# P06_DDR3_Memory.net
KiCad netlist of a schematic drawn in Altium Designer
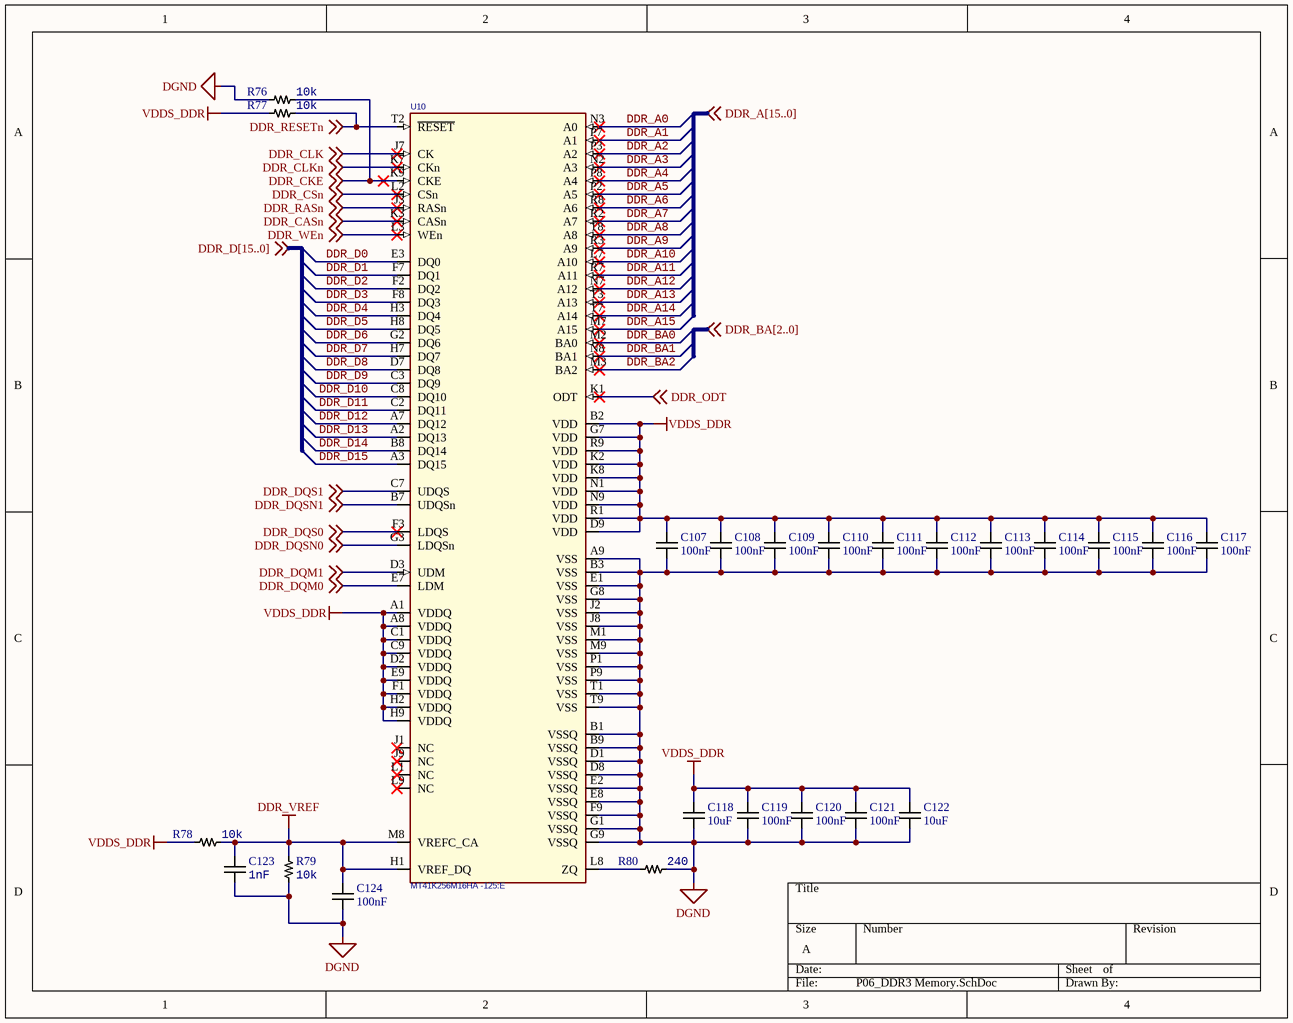
[diagram p0: P06_DDR3 Memory.SchDoc]

(export (version "E")
  (design (tool "Eeschema 10.0.6"))
  (components
    (comp (ref "C107")
      (value "C0402C104K4RACTU")
      (footprint "CAP0402")
      (description "MLCC 100nF 0402 SMD")
      (fields
        (field (name "MANUFACTURER") "KEMET")
        (field (name "CAPACITANCE") "100nF")
        (field (name "TOLERANCE") "10%")
      )
      (libsource (lib "Orient2") (part "CAP_100nF"))
    )
    (comp (ref "C108")
      (value "C0402C104K4RACTU")
      (footprint "CAP0402")
      (description "MLCC 100nF 0402 SMD")
      (fields
        (field (name "MANUFACTURER") "KEMET")
        (field (name "CAPACITANCE") "100nF")
        (field (name "TOLERANCE") "10%")
      )
      (libsource (lib "Orient2") (part "CAP_100nF"))
    )
    (comp (ref "C109")
      (value "C0402C104K4RACTU")
      (footprint "CAP0402")
      (description "MLCC 100nF 0402 SMD")
      (fields
        (field (name "MANUFACTURER") "KEMET")
        (field (name "CAPACITANCE") "100nF")
        (field (name "TOLERANCE") "10%")
      )
      (libsource (lib "Orient2") (part "CAP_100nF"))
    )
    (comp (ref "C110")
      (value "C0402C104K4RACTU")
      (footprint "CAP0402")
      (description "MLCC 100nF 0402 SMD")
      (fields
        (field (name "MANUFACTURER") "KEMET")
        (field (name "CAPACITANCE") "100nF")
        (field (name "TOLERANCE") "10%")
      )
      (libsource (lib "Orient2") (part "CAP_100nF"))
    )
    (comp (ref "C111")
      (value "C0402C104K4RACTU")
      (footprint "CAP0402")
      (description "MLCC 100nF 0402 SMD")
      (fields
        (field (name "MANUFACTURER") "KEMET")
        (field (name "CAPACITANCE") "100nF")
        (field (name "TOLERANCE") "10%")
      )
      (libsource (lib "Orient2") (part "CAP_100nF"))
    )
    (comp (ref "C112")
      (value "C0402C104K4RACTU")
      (footprint "CAP0402")
      (description "MLCC 100nF 0402 SMD")
      (fields
        (field (name "MANUFACTURER") "KEMET")
        (field (name "CAPACITANCE") "100nF")
        (field (name "TOLERANCE") "10%")
      )
      (libsource (lib "Orient2") (part "CAP_100nF"))
    )
    (comp (ref "C113")
      (value "C0402C104K4RACTU")
      (footprint "CAP0402")
      (description "MLCC 100nF 0402 SMD")
      (fields
        (field (name "MANUFACTURER") "KEMET")
        (field (name "CAPACITANCE") "100nF")
        (field (name "TOLERANCE") "10%")
      )
      (libsource (lib "Orient2") (part "CAP_100nF"))
    )
    (comp (ref "C114")
      (value "C0402C104K4RACTU")
      (footprint "CAP0402")
      (description "MLCC 100nF 0402 SMD")
      (fields
        (field (name "MANUFACTURER") "KEMET")
        (field (name "CAPACITANCE") "100nF")
        (field (name "TOLERANCE") "10%")
      )
      (libsource (lib "Orient2") (part "CAP_100nF"))
    )
    (comp (ref "C115")
      (value "C0402C104K4RACTU")
      (footprint "CAP0402")
      (description "MLCC 100nF 0402 SMD")
      (fields
        (field (name "MANUFACTURER") "KEMET")
        (field (name "CAPACITANCE") "100nF")
        (field (name "TOLERANCE") "10%")
      )
      (libsource (lib "Orient2") (part "CAP_100nF"))
    )
    (comp (ref "C116")
      (value "C0402C104K4RACTU")
      (footprint "CAP0402")
      (description "MLCC 100nF 0402 SMD")
      (fields
        (field (name "MANUFACTURER") "KEMET")
        (field (name "CAPACITANCE") "100nF")
        (field (name "TOLERANCE") "10%")
      )
      (libsource (lib "Orient2") (part "CAP_100nF"))
    )
    (comp (ref "C117")
      (value "C0402C104K4RACTU")
      (footprint "CAP0402")
      (description "MLCC 100nF 0402 SMD")
      (fields
        (field (name "MANUFACTURER") "KEMET")
        (field (name "CAPACITANCE") "100nF")
        (field (name "TOLERANCE") "10%")
      )
      (libsource (lib "Orient2") (part "CAP_100nF"))
    )
    (comp (ref "C118")
      (value "C2012X6S1A106K085AC")
      (footprint "CAP0805")
      (description "MLCC 10uF 0805 SMD")
      (fields
        (field (name "MANUFACTURER") "TDK")
        (field (name "CAPACITANCE") "10uF")
        (field (name "TOLERANCE") "10%")
      )
      (libsource (lib "Orient2") (part "CAP_10uF"))
    )
    (comp (ref "C119")
      (value "C0402C104K4RACTU")
      (footprint "CAP0402")
      (description "MLCC 100nF 0402 SMD")
      (fields
        (field (name "MANUFACTURER") "KEMET")
        (field (name "CAPACITANCE") "100nF")
        (field (name "TOLERANCE") "10%")
      )
      (libsource (lib "Orient2") (part "CAP_100nF"))
    )
    (comp (ref "C120")
      (value "C0402C104K4RACTU")
      (footprint "CAP0402")
      (description "MLCC 100nF 0402 SMD")
      (fields
        (field (name "MANUFACTURER") "KEMET")
        (field (name "CAPACITANCE") "100nF")
        (field (name "TOLERANCE") "10%")
      )
      (libsource (lib "Orient2") (part "CAP_100nF"))
    )
    (comp (ref "C121")
      (value "C0402C104K4RACTU")
      (footprint "CAP0402")
      (description "MLCC 100nF 0402 SMD")
      (fields
        (field (name "MANUFACTURER") "KEMET")
        (field (name "CAPACITANCE") "100nF")
        (field (name "TOLERANCE") "10%")
      )
      (libsource (lib "Orient2") (part "CAP_100nF"))
    )
    (comp (ref "C122")
      (value "C2012X6S1A106K085AC")
      (footprint "CAP0805")
      (description "MLCC 10uF 0805 SMD")
      (fields
        (field (name "MANUFACTURER") "TDK")
        (field (name "CAPACITANCE") "10uF")
        (field (name "TOLERANCE") "10%")
      )
      (libsource (lib "Orient2") (part "CAP_10uF"))
    )
    (comp (ref "C123")
      (value "CC0402KRX7R9BB102")
      (footprint "CAP0402")
      (description "MLCC 1nF 0402 SMD")
      (fields
        (field (name "MANUFACTURER") "Yageo")
        (field (name "TOLERANCE") "10%")
        (field (name "CAPACITANCE") "1nF")
      )
      (libsource (lib "Orient2") (part "CAP_1nF"))
    )
    (comp (ref "C124")
      (value "C0402C104K4RACTU")
      (footprint "CAP0402")
      (description "MLCC 100nF 0402 SMD")
      (fields
        (field (name "MANUFACTURER") "KEMET")
        (field (name "CAPACITANCE") "100nF")
        (field (name "TOLERANCE") "10%")
      )
      (libsource (lib "Orient2") (part "CAP_100nF"))
    )
    (comp (ref "R76")
      (value "RC0402FR-0710KL")
      (footprint "RES0402")
      (description "Resistor 10kOhm 0402 SMD")
      (fields
        (field (name "MANUFACTURER") "Yageo")
        (field (name "TOLERANCE") "1%")
        (field (name "RESISTANCE") "10k")
      )
      (libsource (lib "Orient2") (part "RES_10k"))
    )
    (comp (ref "R77")
      (value "RC0402FR-0710KL")
      (footprint "RES0402")
      (description "Resistor 10kOhm 0402 SMD")
      (fields
        (field (name "MANUFACTURER") "Yageo")
        (field (name "TOLERANCE") "1%")
        (field (name "RESISTANCE") "10k")
      )
      (libsource (lib "Orient2") (part "RES_10k"))
    )
    (comp (ref "R78")
      (value "RC0402FR-0710KL")
      (footprint "RES0402")
      (description "Resistor 10kOhm 0402 SMD")
      (fields
        (field (name "MANUFACTURER") "Yageo")
        (field (name "TOLERANCE") "1%")
        (field (name "RESISTANCE") "10k")
      )
      (libsource (lib "Orient2") (part "RES_10k"))
    )
    (comp (ref "R79")
      (value "RC0402FR-0710KL")
      (footprint "RES0402")
      (description "Resistor 10kOhm 0402 SMD")
      (fields
        (field (name "MANUFACTURER") "Yageo")
        (field (name "TOLERANCE") "1%")
        (field (name "RESISTANCE") "10k")
      )
      (libsource (lib "Orient2") (part "RES_10k"))
    )
    (comp (ref "R80")
      (value "RC0402FR-07240RL")
      (footprint "RES0402")
      (description "Resistor 240Ohm 0402 SMD")
      (fields
        (field (name "MANUFACTURER") "Yageo Phycomp")
        (field (name "TOLERANCE") "1%")
        (field (name "RESISTANCE") "240")
      )
      (libsource (lib "Orient2") (part "RES_240"))
    )
    (comp (ref "U10")
      (value "MT41K256M16HA -125:E")
      (footprint "BGA96_T9_P8_9X14")
      (description "DDR2 SDRAM 2Gb (256Mx8)")
      (fields
        (field (name "MANUFACTURER") "Micron Technology")
        (field (name "MANUFACTURER PART NUMBER") "MT41K256M16HA-125:E")
      )
      (libsource (lib "Orient2") (part "MT41K256M16HA"))
    )
  )
  (nets
    (net (code "1") (name "DDR_A0") (class "Default")
      (node (ref "U10") (pin "N3") (pinfunction "A0_N3") (pintype "input+no_connect"))
    )
    (net (code "2") (name "DDR_A1") (class "Default")
      (node (ref "U10") (pin "P7") (pinfunction "A1_P7") (pintype "input+no_connect"))
    )
    (net (code "3") (name "DDR_A2") (class "Default")
      (node (ref "U10") (pin "P3") (pinfunction "A2_P3") (pintype "input+no_connect"))
    )
    (net (code "4") (name "DDR_A3") (class "Default")
      (node (ref "U10") (pin "N2") (pinfunction "A3_N2") (pintype "input+no_connect"))
    )
    (net (code "5") (name "DDR_A4") (class "Default")
      (node (ref "U10") (pin "P8") (pinfunction "A4_P8") (pintype "input+no_connect"))
    )
    (net (code "6") (name "DDR_A5") (class "Default")
      (node (ref "U10") (pin "P2") (pinfunction "A5_P2") (pintype "input+no_connect"))
    )
    (net (code "7") (name "DDR_A6") (class "Default")
      (node (ref "U10") (pin "R8") (pinfunction "A6_R8") (pintype "input+no_connect"))
    )
    (net (code "8") (name "DDR_A7") (class "Default")
      (node (ref "U10") (pin "R2") (pinfunction "A7_R2") (pintype "input+no_connect"))
    )
    (net (code "9") (name "DDR_A8") (class "Default")
      (node (ref "U10") (pin "T8") (pinfunction "A8_T8") (pintype "input+no_connect"))
    )
    (net (code "10") (name "DDR_A9") (class "Default")
      (node (ref "U10") (pin "R3") (pinfunction "A9_R3") (pintype "input+no_connect"))
    )
    (net (code "11") (name "DDR_A10") (class "Default")
      (node (ref "U10") (pin "L7") (pinfunction "A10_L7") (pintype "input+no_connect"))
    )
    (net (code "12") (name "DDR_A11") (class "Default")
      (node (ref "U10") (pin "R7") (pinfunction "A11_R7") (pintype "input+no_connect"))
    )
    (net (code "13") (name "DDR_A12") (class "Default")
      (node (ref "U10") (pin "N7") (pinfunction "A12_N7") (pintype "input+no_connect"))
    )
    (net (code "14") (name "DDR_A13") (class "Default")
      (node (ref "U10") (pin "T3") (pinfunction "A13_T3") (pintype "input+no_connect"))
    )
    (net (code "15") (name "DDR_A14") (class "Default")
      (node (ref "U10") (pin "T7") (pinfunction "A14_T7") (pintype "input+no_connect"))
    )
    (net (code "16") (name "DDR_A15") (class "Default")
      (node (ref "U10") (pin "M7") (pinfunction "A15_M7") (pintype "input+no_connect"))
    )
    (net (code "18") (name "DDR_BA0") (class "Default")
      (node (ref "U10") (pin "M2") (pinfunction "BA0_M2") (pintype "input+no_connect"))
    )
    (net (code "19") (name "DDR_BA1") (class "Default")
      (node (ref "U10") (pin "N8") (pinfunction "BA1_N8") (pintype "input+no_connect"))
    )
    (net (code "20") (name "DDR_BA2") (class "Default")
      (node (ref "U10") (pin "M3") (pinfunction "BA2_M3") (pintype "input+no_connect"))
    )
    (net (code "22") (name "DDR_CASn") (class "Default")
      (node (ref "U10") (pin "K3") (pinfunction "CASn_K3") (pintype "input"))
    )
    (net (code "23") (name "DDR_CKE") (class "Default")
      (node (ref "R76") (pin "1") (pintype "passive"))
      (node (ref "U10") (pin "K9") (pinfunction "CKE_K9") (pintype "input"))
    )
    (net (code "24") (name "DDR_CLK") (class "Default")
      (node (ref "U10") (pin "J7") (pinfunction "CK_J7") (pintype "input"))
    )
    (net (code "25") (name "DDR_CLKn") (class "Default")
      (node (ref "U10") (pin "K7") (pinfunction "CKn_K7") (pintype "input"))
    )
    (net (code "26") (name "DDR_CSn") (class "Default")
      (node (ref "U10") (pin "L2") (pinfunction "CSn_L2") (pintype "input"))
    )
    (net (code "27") (name "DDR_D0") (class "Default")
      (node (ref "U10") (pin "E3") (pinfunction "DQ0_E3") (pintype "bidirectional"))
    )
    (net (code "28") (name "DDR_D1") (class "Default")
      (node (ref "U10") (pin "F7") (pinfunction "DQ1_F7") (pintype "bidirectional"))
    )
    (net (code "29") (name "DDR_D2") (class "Default")
      (node (ref "U10") (pin "F2") (pinfunction "DQ2_F2") (pintype "bidirectional"))
    )
    (net (code "30") (name "DDR_D3") (class "Default")
      (node (ref "U10") (pin "F8") (pinfunction "DQ3_F8") (pintype "bidirectional"))
    )
    (net (code "31") (name "DDR_D4") (class "Default")
      (node (ref "U10") (pin "H3") (pinfunction "DQ4_H3") (pintype "bidirectional"))
    )
    (net (code "32") (name "DDR_D5") (class "Default")
      (node (ref "U10") (pin "H8") (pinfunction "DQ5_H8") (pintype "bidirectional"))
    )
    (net (code "33") (name "DDR_D6") (class "Default")
      (node (ref "U10") (pin "G2") (pinfunction "DQ6_G2") (pintype "bidirectional"))
    )
    (net (code "34") (name "DDR_D7") (class "Default")
      (node (ref "U10") (pin "H7") (pinfunction "DQ7_H7") (pintype "bidirectional"))
    )
    (net (code "35") (name "DDR_D8") (class "Default")
      (node (ref "U10") (pin "D7") (pinfunction "DQ8_D7") (pintype "bidirectional"))
    )
    (net (code "36") (name "DDR_D9") (class "Default")
      (node (ref "U10") (pin "C3") (pinfunction "DQ9_C3") (pintype "bidirectional"))
    )
    (net (code "37") (name "DDR_D10") (class "Default")
      (node (ref "U10") (pin "C8") (pinfunction "DQ10_C8") (pintype "bidirectional"))
    )
    (net (code "38") (name "DDR_D11") (class "Default")
      (node (ref "U10") (pin "C2") (pinfunction "DQ11_C2") (pintype "bidirectional"))
    )
    (net (code "39") (name "DDR_D12") (class "Default")
      (node (ref "U10") (pin "A7") (pinfunction "DQ12_A7") (pintype "bidirectional"))
    )
    (net (code "40") (name "DDR_D13") (class "Default")
      (node (ref "U10") (pin "A2") (pinfunction "DQ13_A2") (pintype "bidirectional"))
    )
    (net (code "41") (name "DDR_D14") (class "Default")
      (node (ref "U10") (pin "B8") (pinfunction "DQ14_B8") (pintype "bidirectional"))
    )
    (net (code "42") (name "DDR_D15") (class "Default")
      (node (ref "U10") (pin "A3") (pinfunction "DQ15_A3") (pintype "bidirectional"))
    )
    (net (code "43") (name "DDR_DQM0") (class "Default")
      (node (ref "U10") (pin "E7") (pinfunction "LDM_E7") (pintype "bidirectional"))
    )
    (net (code "44") (name "DDR_DQM1") (class "Default")
      (node (ref "U10") (pin "D3") (pinfunction "UDM_D3") (pintype "input"))
    )
    (net (code "45") (name "DDR_DQS0") (class "Default")
      (node (ref "U10") (pin "F3") (pinfunction "LDQS_F3") (pintype "bidirectional"))
    )
    (net (code "46") (name "DDR_DQS1") (class "Default")
      (node (ref "U10") (pin "C7") (pinfunction "UDQS_C7") (pintype "bidirectional"))
    )
    (net (code "47") (name "DDR_DQSN0") (class "Default")
      (node (ref "U10") (pin "G3") (pinfunction "LDQSn_G3") (pintype "bidirectional"))
    )
    (net (code "48") (name "DDR_DQSN1") (class "Default")
      (node (ref "U10") (pin "B7") (pinfunction "UDQSn_B7") (pintype "bidirectional"))
    )
    (net (code "50") (name "DDR_ODT") (class "Default")
      (node (ref "U10") (pin "K1") (pinfunction "ODT_K1") (pintype "input"))
    )
    (net (code "51") (name "DDR_RASn") (class "Default")
      (node (ref "U10") (pin "J3") (pinfunction "RASn_J3") (pintype "input"))
    )
    (net (code "52") (name "DDR_RESETn") (class "Default")
      (node (ref "R77") (pin "1") (pintype "passive"))
      (node (ref "U10") (pin "T2") (pinfunction "~{RESET}_T2") (pintype "input"))
    )
    (net (code "53") (name "DDR_VREF") (class "Default")
      (node (ref "C123") (pin "1") (pintype "passive"))
      (node (ref "C124") (pin "1") (pintype "passive"))
      (node (ref "R78") (pin "1") (pintype "passive"))
      (node (ref "R79") (pin "2") (pintype "passive"))
      (node (ref "U10") (pin "H1") (pinfunction "VREF_DQ_H1") (pintype "passive"))
      (node (ref "U10") (pin "M8") (pinfunction "VREFC_CA_M8") (pintype "power_in"))
    )
    (net (code "54") (name "DDR_WEn") (class "Default")
      (node (ref "U10") (pin "L3") (pinfunction "WEn_L3") (pintype "input"))
    )
    (net (code "55") (name "DGND") (class "Default")
      (node (ref "C107") (pin "2") (pintype "passive"))
      (node (ref "C108") (pin "2") (pintype "passive"))
      (node (ref "C109") (pin "2") (pintype "passive"))
      (node (ref "C110") (pin "2") (pintype "passive"))
      (node (ref "C111") (pin "2") (pintype "passive"))
      (node (ref "C112") (pin "2") (pintype "passive"))
      (node (ref "C113") (pin "2") (pintype "passive"))
      (node (ref "C114") (pin "2") (pintype "passive"))
      (node (ref "C115") (pin "2") (pintype "passive"))
      (node (ref "C116") (pin "2") (pintype "passive"))
      (node (ref "C117") (pin "2") (pintype "passive"))
      (node (ref "C118") (pin "1") (pintype "passive"))
      (node (ref "C119") (pin "2") (pintype "passive"))
      (node (ref "C120") (pin "2") (pintype "passive"))
      (node (ref "C121") (pin "2") (pintype "passive"))
      (node (ref "C122") (pin "1") (pintype "passive"))
      (node (ref "C123") (pin "2") (pintype "passive"))
      (node (ref "C124") (pin "2") (pintype "passive"))
      (node (ref "R76") (pin "2") (pintype "passive"))
      (node (ref "R79") (pin "1") (pintype "passive"))
      (node (ref "R80") (pin "2") (pintype "passive"))
      (node (ref "U10") (pin "A9") (pinfunction "VSS_A9") (pintype "power_in"))
      (node (ref "U10") (pin "B1") (pinfunction "VSSQ_B1") (pintype "power_in"))
      (node (ref "U10") (pin "B3") (pinfunction "VSS_B3") (pintype "power_in"))
      (node (ref "U10") (pin "B9") (pinfunction "VSSQ_B9") (pintype "power_in"))
      (node (ref "U10") (pin "D1") (pinfunction "VSSQ_D1") (pintype "power_in"))
      (node (ref "U10") (pin "D8") (pinfunction "VSSQ_D8") (pintype "power_in"))
      (node (ref "U10") (pin "E1") (pinfunction "VSS_E1") (pintype "power_in"))
      (node (ref "U10") (pin "E2") (pinfunction "VSSQ_E2") (pintype "power_in"))
      (node (ref "U10") (pin "E8") (pinfunction "VSSQ_E8") (pintype "power_in"))
      (node (ref "U10") (pin "F9") (pinfunction "VSSQ_F9") (pintype "power_in"))
      (node (ref "U10") (pin "G1") (pinfunction "VSSQ_G1") (pintype "power_in"))
      (node (ref "U10") (pin "G8") (pinfunction "VSS_G8") (pintype "power_in"))
      (node (ref "U10") (pin "G9") (pinfunction "VSSQ_G9") (pintype "power_in"))
      (node (ref "U10") (pin "J2") (pinfunction "VSS_J2") (pintype "power_in"))
      (node (ref "U10") (pin "J8") (pinfunction "VSS_J8") (pintype "power_in"))
      (node (ref "U10") (pin "M1") (pinfunction "VSS_M1") (pintype "power_in"))
      (node (ref "U10") (pin "M9") (pinfunction "VSS_M9") (pintype "power_in"))
      (node (ref "U10") (pin "P1") (pinfunction "VSS_P1") (pintype "power_in"))
      (node (ref "U10") (pin "P9") (pinfunction "VSS_P9") (pintype "power_in"))
      (node (ref "U10") (pin "T1") (pinfunction "VSS_T1") (pintype "power_in"))
      (node (ref "U10") (pin "T9") (pinfunction "VSS_T9") (pintype "power_in"))
    )
    (net (code "56") (name "Net-(U10-ZQ)") (class "Default")
      (node (ref "R80") (pin "1") (pintype "passive"))
      (node (ref "U10") (pin "L8") (pinfunction "ZQ_L8") (pintype "passive"))
    )
    (net (code "57") (name "VDDS_DDR") (class "Default")
      (node (ref "C107") (pin "1") (pintype "passive"))
      (node (ref "C108") (pin "1") (pintype "passive"))
      (node (ref "C109") (pin "1") (pintype "passive"))
      (node (ref "C110") (pin "1") (pintype "passive"))
      (node (ref "C111") (pin "1") (pintype "passive"))
      (node (ref "C112") (pin "1") (pintype "passive"))
      (node (ref "C113") (pin "1") (pintype "passive"))
      (node (ref "C114") (pin "1") (pintype "passive"))
      (node (ref "C115") (pin "1") (pintype "passive"))
      (node (ref "C116") (pin "1") (pintype "passive"))
      (node (ref "C117") (pin "1") (pintype "passive"))
      (node (ref "C118") (pin "2") (pintype "passive"))
      (node (ref "C119") (pin "1") (pintype "passive"))
      (node (ref "C120") (pin "1") (pintype "passive"))
      (node (ref "C121") (pin "1") (pintype "passive"))
      (node (ref "C122") (pin "2") (pintype "passive"))
      (node (ref "R77") (pin "2") (pintype "passive"))
      (node (ref "R78") (pin "2") (pintype "passive"))
      (node (ref "U10") (pin "A1") (pinfunction "VDDQ_A1") (pintype "power_in"))
      (node (ref "U10") (pin "A8") (pinfunction "VDDQ_A8") (pintype "power_in"))
      (node (ref "U10") (pin "B2") (pinfunction "VDD_B2") (pintype "power_in"))
      (node (ref "U10") (pin "C1") (pinfunction "VDDQ_C1") (pintype "power_in"))
      (node (ref "U10") (pin "C9") (pinfunction "VDDQ_C9") (pintype "power_in"))
      (node (ref "U10") (pin "D2") (pinfunction "VDDQ_D2") (pintype "power_in"))
      (node (ref "U10") (pin "D9") (pinfunction "VDD_D9") (pintype "power_in"))
      (node (ref "U10") (pin "E9") (pinfunction "VDDQ_E9") (pintype "power_in"))
      (node (ref "U10") (pin "F1") (pinfunction "VDDQ_F1") (pintype "power_in"))
      (node (ref "U10") (pin "G7") (pinfunction "VDD_G7") (pintype "power_in"))
      (node (ref "U10") (pin "H2") (pinfunction "VDDQ_H2") (pintype "power_in"))
      (node (ref "U10") (pin "H9") (pinfunction "VDDQ_H9") (pintype "power_in"))
      (node (ref "U10") (pin "K2") (pinfunction "VDD_K2") (pintype "power_in"))
      (node (ref "U10") (pin "K8") (pinfunction "VDD_K8") (pintype "power_in"))
      (node (ref "U10") (pin "N1") (pinfunction "VDD_N1") (pintype "power_in"))
      (node (ref "U10") (pin "N9") (pinfunction "VDD_N9") (pintype "power_in"))
      (node (ref "U10") (pin "R1") (pinfunction "VDD_R1") (pintype "power_in"))
      (node (ref "U10") (pin "R9") (pinfunction "VDD_R9") (pintype "power_in"))
    )
    (net (code "58") (name "unconnected-(U10-NC-PadJ1)") (class "Default")
      (node (ref "U10") (pin "J1") (pinfunction "NC_J1") (pintype "passive+no_connect"))
    )
    (net (code "59") (name "unconnected-(U10-NC-PadJ9)") (class "Default")
      (node (ref "U10") (pin "J9") (pinfunction "NC_J9") (pintype "passive+no_connect"))
    )
    (net (code "60") (name "unconnected-(U10-NC-PadL1)") (class "Default")
      (node (ref "U10") (pin "L1") (pinfunction "NC_L1") (pintype "power_in+no_connect"))
    )
    (net (code "61") (name "unconnected-(U10-NC-PadL9)") (class "Default")
      (node (ref "U10") (pin "L9") (pinfunction "NC_L9") (pintype "power_in+no_connect"))
    )
  )
)
